# CNTL.net
KiCad netlist of a schematic drawn in Altium Designer
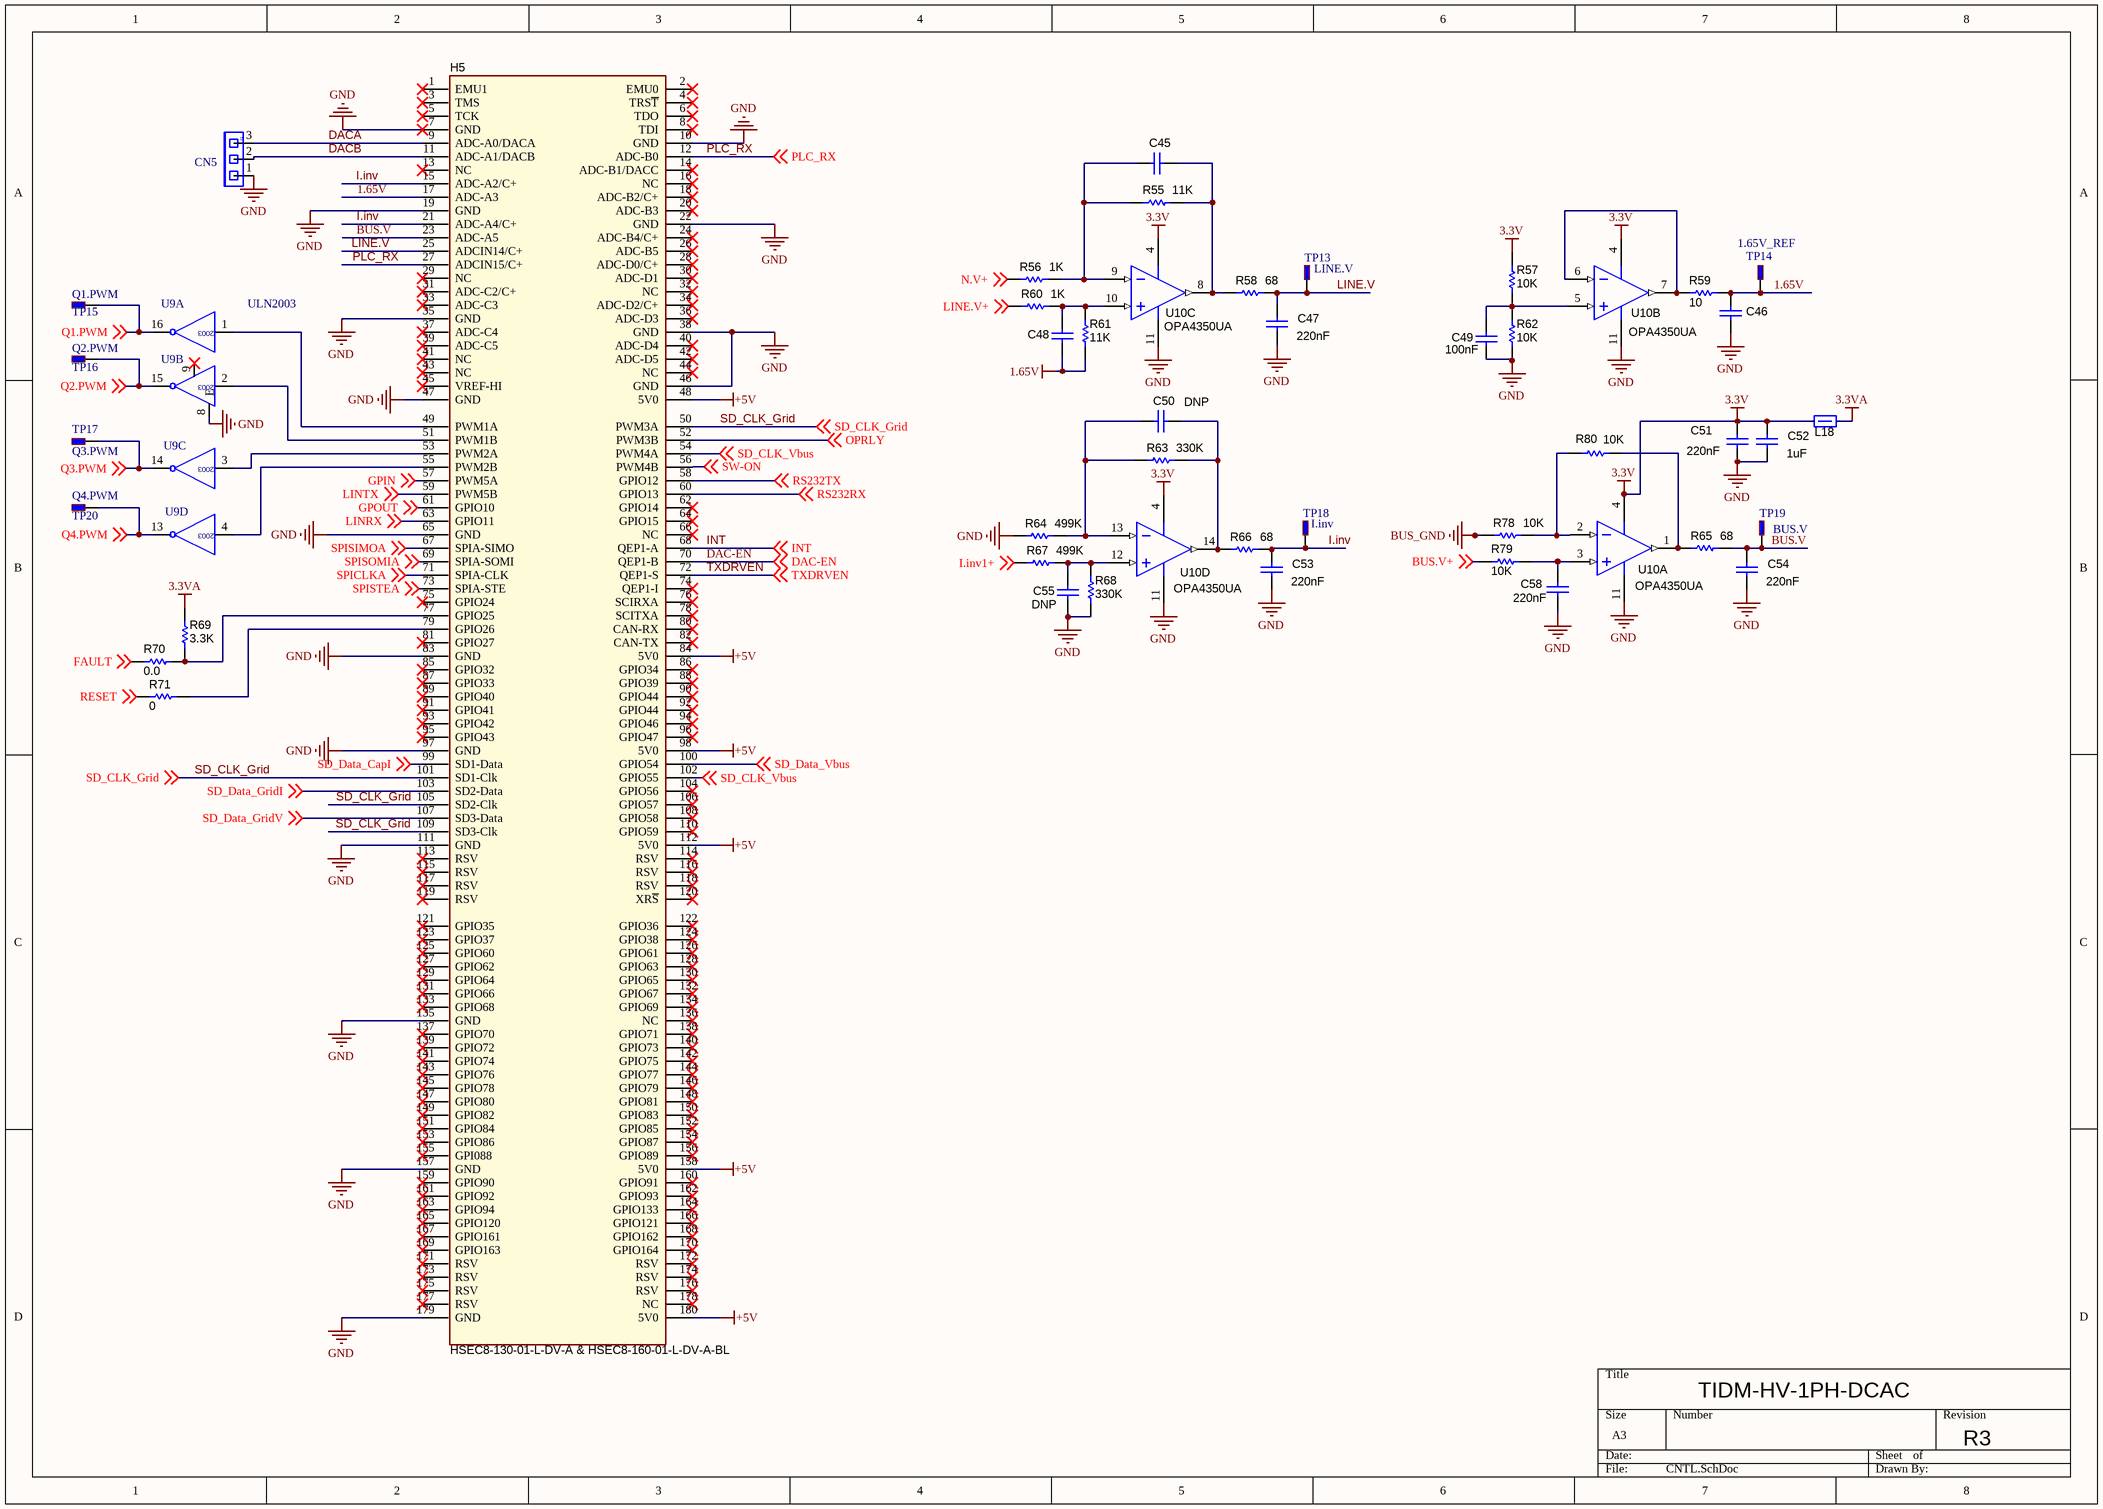
[diagram p0: CNTL.SchDoc]

(export (version "E")
  (design (tool "Eeschema 10.0.6"))
  (components
    (comp (ref "C45")
      (value "Used in BOM report")
      (footprint "0603")
      (description "CAP, CERM, xxxF, xxV, [TempCo], xx%, [PackageReference]")
      (fields (field (name "PUBLISHER") "Texas Instruments"))
      (libsource (lib "MiscParts") (part "Capacitor"))
    )
    (comp (ref "C46")
      (value "Used in BOM report")
      (footprint "0603")
      (description "CAP, CERM, xxxF, xxV, [TempCo], xx%, [PackageReference]")
      (fields (field (name "PUBLISHER") "Texas Instruments"))
      (libsource (lib "MiscParts") (part "Capacitor"))
    )
    (comp (ref "C47")
      (value "220nF")
      (footprint "0603")
      (description "CAP, CERM, xxxF, xxV, [TempCo], xx%, [PackageReference]")
      (fields
        (field (name "MANUFACTURER") "Used in BOM report")
        (field (name "PUBLISHER") "Texas Instruments")
      )
      (libsource (lib "MiscParts") (part "Capacitor"))
    )
    (comp (ref "C48")
      (value "Used in BOM report")
      (footprint "0603")
      (description "CAP, CERM, xxxF, xxV, [TempCo], xx%, [PackageReference]")
      (fields (field (name "PUBLISHER") "Texas Instruments"))
      (libsource (lib "MiscParts") (part "Capacitor"))
    )
    (comp (ref "C49")
      (value "100nF")
      (footprint "0603")
      (description "CAP, CERM, xxxF, xxV, [TempCo], xx%, [PackageReference]")
      (fields
        (field (name "MANUFACTURER") "Used in BOM report")
        (field (name "PUBLISHER") "Texas Instruments")
      )
      (libsource (lib "MiscParts") (part "Capacitor"))
    )
    (comp (ref "C50")
      (value "DNP")
      (footprint "0603")
      (description "CAP, CERM, xxxF, xxV, [TempCo], xx%, [PackageReference]")
      (fields
        (field (name "MANUFACTURER") "Used in BOM report")
        (field (name "PUBLISHER") "Texas Instruments")
      )
      (libsource (lib "MiscParts") (part "Capacitor"))
    )
    (comp (ref "C51")
      (value "220nF")
      (footprint "0603")
      (description "CAP, CERM, xxxF, xxV, [TempCo], xx%, [PackageReference]")
      (fields
        (field (name "MANUFACTURER") "Used in BOM report")
        (field (name "PUBLISHER") "Texas Instruments")
      )
      (libsource (lib "MiscParts") (part "Capacitor"))
    )
    (comp (ref "C52")
      (value "1uF")
      (footprint "0603")
      (description "CAP, CERM, xxxF, xxV, [TempCo], xx%, [PackageReference]")
      (fields
        (field (name "MANUFACTURER") "Used in BOM report")
        (field (name "PUBLISHER") "Texas Instruments")
      )
      (libsource (lib "MiscParts") (part "Capacitor"))
    )
    (comp (ref "C53")
      (value "220nF")
      (footprint "0603")
      (description "CAP, CERM, xxxF, xxV, [TempCo], xx%, [PackageReference]")
      (fields
        (field (name "MANUFACTURER") "Used in BOM report")
        (field (name "PUBLISHER") "Texas Instruments")
      )
      (libsource (lib "MiscParts") (part "Capacitor"))
    )
    (comp (ref "C54")
      (value "220nF")
      (footprint "0603")
      (description "CAP, CERM, xxxF, xxV, [TempCo], xx%, [PackageReference]")
      (fields
        (field (name "MANUFACTURER") "Used in BOM report")
        (field (name "PUBLISHER") "Texas Instruments")
      )
      (libsource (lib "MiscParts") (part "Capacitor"))
    )
    (comp (ref "C55")
      (value "DNP")
      (footprint "0603")
      (description "CAP, CERM, xxxF, xxV, [TempCo], xx%, [PackageReference]")
      (fields
        (field (name "MANUFACTURER") "Used in BOM report")
        (field (name "PUBLISHER") "Texas Instruments")
      )
      (libsource (lib "MiscParts") (part "Capacitor"))
    )
    (comp (ref "C58")
      (value "220nF")
      (footprint "0603")
      (description "CAP, CERM, xxxF, xxV, [TempCo], xx%, [PackageReference]")
      (fields
        (field (name "MANUFACTURER") "Used in BOM report")
        (field (name "PUBLISHER") "Texas Instruments")
      )
      (libsource (lib "MiscParts") (part "Capacitor"))
    )
    (comp (ref "CN5")
      (value "SCI_PORT")
      (footprint "HDR1X3")
      (description "DB01P03")
      (libsource (lib "AD-DIPWIN") (part "DB01P03"))
    )
    (comp (ref "H5")
      (value "HSEC8-130-01-L-DV-A & HSEC8-160-01-L-DV-A-BL")
      (footprint "HEADER_HSEC8_180_DV")
      (fields (field (name "MANUFACTURER") "Samtech") (field (name "SYMBOLCREATOR") "Use a-id"))
      (libsource (lib "controlCARDDockingStationR4_1") (part "HEADER_HSEC_180_F2837x_HVDCACSolar"))
    )
    (comp (ref "L18")
      (value "LQM21FN220N00L")
      (footprint "0805")
      (description "Ferrite Bead, 30 ohm @ 100MHz, 1.5A, 0805")
      (fields (field (name "MANUFACTURER") "Murata") (field (name "PUBLISHER") "Texas Instruments"))
      (libsource (lib "FerriteBead") (part "MMZ2012R300A"))
    )
    (comp (ref "R55")
      (value "11K")
      (footprint "0603")
      (description "RES, 1K ohm, x%, xW, [PackageReference]")
      (fields
        (field (name "MANUFACTURER") "Used in BOM report")
        (field (name "PUBLISHER") "Texas Instruments")
      )
      (libsource (lib "MiscParts") (part "Resistor"))
    )
    (comp (ref "R56")
      (value "1K")
      (footprint "0603")
      (description "RES, 1K ohm, x%, xW, [PackageReference]")
      (fields
        (field (name "MANUFACTURER") "Used in BOM report")
        (field (name "PUBLISHER") "Texas Instruments")
      )
      (libsource (lib "MiscParts") (part "Resistor"))
    )
    (comp (ref "R57")
      (value "10K")
      (footprint "0603")
      (description "RES, 10K ohm, x%, xW, [PackageReference]")
      (fields
        (field (name "MANUFACTURER") "Used in BOM report")
        (field (name "PUBLISHER") "Texas Instruments")
      )
      (libsource (lib "MiscParts") (part "Resistor"))
    )
    (comp (ref "R58")
      (value "68")
      (footprint "0603")
      (description "RES, 1K ohm, x%, xW, [PackageReference]")
      (fields
        (field (name "MANUFACTURER") "Used in BOM report")
        (field (name "PUBLISHER") "Texas Instruments")
      )
      (libsource (lib "MiscParts") (part "Resistor"))
    )
    (comp (ref "R59")
      (value "10")
      (footprint "0603")
      (description "RES, 1K ohm, x%, xW, [PackageReference]")
      (fields
        (field (name "MANUFACTURER") "Used in BOM report")
        (field (name "PUBLISHER") "Texas Instruments")
      )
      (libsource (lib "MiscParts") (part "Resistor"))
    )
    (comp (ref "R60")
      (value "1K")
      (footprint "0603")
      (description "RES, 1K ohm, x%, xW, [PackageReference]")
      (fields
        (field (name "MANUFACTURER") "Used in BOM report")
        (field (name "PUBLISHER") "Texas Instruments")
      )
      (libsource (lib "MiscParts") (part "Resistor"))
    )
    (comp (ref "R61")
      (value "11K")
      (footprint "0603")
      (description "RES, 1K ohm, x%, xW, [PackageReference]")
      (fields
        (field (name "MANUFACTURER") "Used in BOM report")
        (field (name "PUBLISHER") "Texas Instruments")
      )
      (libsource (lib "MiscParts") (part "Resistor"))
    )
    (comp (ref "R62")
      (value "10K")
      (footprint "0603")
      (description "RES, 10K ohm, x%, xW, [PackageReference]")
      (fields
        (field (name "MANUFACTURER") "Used in BOM report")
        (field (name "PUBLISHER") "Texas Instruments")
      )
      (libsource (lib "MiscParts") (part "Resistor"))
    )
    (comp (ref "R63")
      (value "330K")
      (footprint "0603")
      (description "RES, 330K ohm, x%, xW, [PackageReference]")
      (fields
        (field (name "MANUFACTURER") "Used in BOM report")
        (field (name "PUBLISHER") "Texas Instruments")
      )
      (libsource (lib "MiscParts") (part "Resistor"))
    )
    (comp (ref "R64")
      (value "499K")
      (footprint "0603")
      (description "RES, 499K ohm, x%, xW, [PackageReference]")
      (fields
        (field (name "MANUFACTURER") "Used in BOM report")
        (field (name "PUBLISHER") "Texas Instruments")
      )
      (libsource (lib "MiscParts") (part "Resistor"))
    )
    (comp (ref "R65")
      (value "68")
      (footprint "0603")
      (description "RES, 1K ohm, x%, xW, [PackageReference]")
      (fields
        (field (name "MANUFACTURER") "Used in BOM report")
        (field (name "PUBLISHER") "Texas Instruments")
      )
      (libsource (lib "MiscParts") (part "Resistor"))
    )
    (comp (ref "R66")
      (value "68")
      (footprint "0603")
      (description "RES, 1K ohm, x%, xW, [PackageReference]")
      (fields
        (field (name "MANUFACTURER") "Used in BOM report")
        (field (name "PUBLISHER") "Texas Instruments")
      )
      (libsource (lib "MiscParts") (part "Resistor"))
    )
    (comp (ref "R67")
      (value "499K")
      (footprint "0603")
      (description "RES, 499K ohm, x%, xW, [PackageReference]")
      (fields
        (field (name "MANUFACTURER") "Used in BOM report")
        (field (name "PUBLISHER") "Texas Instruments")
      )
      (libsource (lib "MiscParts") (part "Resistor"))
    )
    (comp (ref "R68")
      (value "330K")
      (footprint "0603")
      (description "RES, 330K ohm, x%, xW, [PackageReference]")
      (fields
        (field (name "MANUFACTURER") "Used in BOM report")
        (field (name "PUBLISHER") "Texas Instruments")
      )
      (libsource (lib "MiscParts") (part "Resistor"))
    )
    (comp (ref "R69")
      (value "3.3K")
      (footprint "0805")
      (description "RES, 3.3Kohm, 5%, 0.125W, 0805")
      (fields
        (field (name "PARTNUMBER") "RC0805JR-071R1L")
        (field (name "MANUFACTURER") "Yageo America")
        (field (name "PUBLISHER") "Texas Instruments")
      )
      (libsource (lib "Resistor_0805") (part "RC0805JR-071R1L"))
    )
    (comp (ref "R70")
      (value "0.0")
      (footprint "0805")
      (description "RES, 0 ohm, 5%, 0.125W, 0805")
      (fields
        (field (name "PARTNUMBER") "RC0805JR-071R1L")
        (field (name "MANUFACTURER") "Yageo America")
        (field (name "PUBLISHER") "Texas Instruments")
      )
      (libsource (lib "Resistor_0805") (part "RC0805JR-071R1L"))
    )
    (comp (ref "R71")
      (value "0")
      (footprint "0805")
      (description "RES, 0.0 ohm, 5%, 0.125W, 0805")
      (fields
        (field (name "PARTNUMBER") "RC0805JR-071R1L")
        (field (name "MANUFACTURER") "Yageo America")
        (field (name "PUBLISHER") "Texas Instruments")
      )
      (libsource (lib "Resistor_0805") (part "RC0805JR-071R1L"))
    )
    (comp (ref "R78")
      (value "10K")
      (footprint "0603")
      (description "RES, 1K ohm, x%, xW, [PackageReference]")
      (fields
        (field (name "MANUFACTURER") "Used in BOM report")
        (field (name "PUBLISHER") "Texas Instruments")
      )
      (libsource (lib "MiscParts") (part "Resistor"))
    )
    (comp (ref "R79")
      (value "10K")
      (footprint "0603")
      (description "RES, 1K ohm, x%, xW, [PackageReference]")
      (fields
        (field (name "MANUFACTURER") "Used in BOM report")
        (field (name "PUBLISHER") "Texas Instruments")
      )
      (libsource (lib "MiscParts") (part "Resistor"))
    )
    (comp (ref "R80")
      (value "10K")
      (footprint "0603")
      (description "RES, 1K ohm, x%, xW, [PackageReference]")
      (fields
        (field (name "MANUFACTURER") "Used in BOM report")
        (field (name "PUBLISHER") "Texas Instruments")
      )
      (libsource (lib "MiscParts") (part "Resistor"))
    )
    (comp (ref "TP13")
      (value "LINE.V")
      (footprint "PIN1")
      (description "ZR")
      (libsource (lib "*") (part "PIN1"))
    )
    (comp (ref "TP14")
      (value "1.65V_REF")
      (footprint "PIN1")
      (description "ZR")
      (libsource (lib "*") (part "PIN1"))
    )
    (comp (ref "TP15")
      (value "Q1.PWM")
      (footprint "PIN1")
      (description "ZR")
      (libsource (lib "") (part "PIN1_2"))
    )
    (comp (ref "TP16")
      (value "Q2.PWM")
      (footprint "PIN1")
      (description "ZR")
      (libsource (lib "") (part "PIN1_1"))
    )
    (comp (ref "TP17")
      (value "Q3.PWM")
      (footprint "PIN1")
      (description "ZR")
      (libsource (lib "") (part "PIN1_2"))
    )
    (comp (ref "TP18")
      (value "I.inv")
      (footprint "PIN1")
      (description "ZR")
      (libsource (lib "*") (part "PIN1"))
    )
    (comp (ref "TP19")
      (value "BUS.V")
      (footprint "PIN1")
      (description "ZR")
      (libsource (lib "*") (part "PIN1"))
    )
    (comp (ref "TP20")
      (value "Q4.PWM")
      (footprint "PIN1")
      (description "ZR")
      (libsource (lib "") (part "PIN1_1"))
    )
    (comp (ref "U9")
      (value "ULN2003")
      (footprint "2003SM")
      (description "2003SM")
      (libsource (lib "") (part "2003SM_1"))
    )
    (comp (ref "U10")
      (value "OPA4350UA")
      (footprint "D0014A_N")
      (fields
        (field (name "MANUFACTURER") "Texas Instruments")
        (field (name "ALTERNATE PARTNUMBER") "Equivalent")
      )
      (libsource (lib "TI Amplifiers and Linear Operational Amplifier Precision Amplifier Part One") (part "OPA4350UA"))
    )
  )
  (nets
    (net (code "1") (name "+5V") (class "Default")
      (node (ref "H5") (pin "112") (pinfunction "5V0_112") (pintype "passive"))
      (node (ref "H5") (pin "158") (pinfunction "5V0_158") (pintype "passive"))
      (node (ref "H5") (pin "180") (pinfunction "5V0_180") (pintype "passive"))
      (node (ref "H5") (pin "48") (pinfunction "5V0_48") (pintype "passive"))
      (node (ref "H5") (pin "84") (pinfunction "5V0_84") (pintype "passive"))
      (node (ref "H5") (pin "98") (pinfunction "5V0_98") (pintype "passive"))
    )
    (net (code "3") (name "/BUS.V") (class "Default")
      (node (ref "C54") (pin "1") (pinfunction "1_1") (pintype "passive"))
      (node (ref "H5") (pin "23") (pinfunction "ADC-A5_23") (pintype "passive"))
      (node (ref "R65") (pin "2") (pinfunction "2_2") (pintype "passive"))
      (node (ref "TP19") (pin "1") (pinfunction "1_1") (pintype "passive"))
    )
    (net (code "4") (name "/DACA") (class "Default")
      (node (ref "CN5") (pin "3") (pintype "passive"))
      (node (ref "H5") (pin "9") (pinfunction "ADC-A0/DACA_9") (pintype "passive"))
    )
    (net (code "5") (name "/DACB") (class "Default")
      (node (ref "CN5") (pin "2") (pintype "passive"))
      (node (ref "H5") (pin "11") (pinfunction "ADC-A1/DACB_11") (pintype "passive"))
    )
    (net (code "6") (name "/I.inv") (class "Default")
      (node (ref "C53") (pin "1") (pinfunction "1_1") (pintype "passive"))
      (node (ref "H5") (pin "15") (pinfunction "ADC-A2/C+_15") (pintype "passive"))
      (node (ref "H5") (pin "21") (pinfunction "ADC-A4/C+_21") (pintype "passive"))
      (node (ref "R66") (pin "2") (pinfunction "2_2") (pintype "passive"))
      (node (ref "TP18") (pin "1") (pinfunction "1_1") (pintype "passive"))
    )
    (net (code "7") (name "/LINE.V") (class "Default")
      (node (ref "C47") (pin "1") (pinfunction "1_1") (pintype "passive"))
      (node (ref "H5") (pin "25") (pinfunction "ADCIN14/C+_25") (pintype "passive"))
      (node (ref "R58") (pin "2") (pinfunction "2_2") (pintype "passive"))
      (node (ref "TP13") (pin "1") (pinfunction "1_1") (pintype "passive"))
    )
    (net (code "8") (name "1.65V") (class "Default")
      (node (ref "C46") (pin "1") (pinfunction "1_1") (pintype "passive"))
      (node (ref "C48") (pin "2") (pinfunction "2_2") (pintype "passive"))
      (node (ref "H5") (pin "17") (pinfunction "ADC-A3_17") (pintype "passive"))
      (node (ref "R59") (pin "1") (pinfunction "1_1") (pintype "passive"))
      (node (ref "R61") (pin "1") (pinfunction "1_1") (pintype "passive"))
      (node (ref "TP14") (pin "1") (pinfunction "1_1") (pintype "passive"))
    )
    (net (code "9") (name "3.3V") (class "Default")
      (node (ref "C51") (pin "1") (pinfunction "1_1") (pintype "passive"))
      (node (ref "C52") (pin "1") (pinfunction "1_1") (pintype "passive"))
      (node (ref "L18") (pin "2") (pinfunction "2_2") (pintype "passive"))
      (node (ref "R57") (pin "2") (pinfunction "2_2") (pintype "passive"))
      (node (ref "U10") (pin "4") (pinfunction "V+_4") (pintype "power_in"))
    )
    (net (code "10") (name "3.3VA") (class "Default")
      (node (ref "L18") (pin "1") (pinfunction "1_1") (pintype "passive"))
      (node (ref "R69") (pin "2") (pinfunction "2_2") (pintype "passive"))
    )
    (net (code "11") (name "BUS.V+") (class "Default")
      (node (ref "R79") (pin "2") (pinfunction "2_2") (pintype "passive"))
    )
    (net (code "12") (name "BUS_GND") (class "Default")
      (node (ref "R78") (pin "1") (pinfunction "1_1") (pintype "passive"))
    )
    (net (code "13") (name "COM") (class "Default")
      (node (ref "U9") (pin "9") (pinfunction "COM_9") (pintype "power_in"))
    )
    (net (code "14") (name "DAC-EN") (class "Default")
      (node (ref "H5") (pin "70") (pinfunction "QEP1-B_70") (pintype "passive"))
    )
    (net (code "15") (name "E") (class "Default")
      (node (ref "U9") (pin "8") (pinfunction "E_8") (pintype "power_in"))
    )
    (net (code "16") (name "FAULT") (class "Default")
      (node (ref "R70") (pin "1") (pinfunction "1_1") (pintype "passive"))
    )
    (net (code "17") (name "GND") (class "Default")
      (node (ref "C46") (pin "2") (pinfunction "2_2") (pintype "passive"))
      (node (ref "C47") (pin "2") (pinfunction "2_2") (pintype "passive"))
      (node (ref "C49") (pin "2") (pinfunction "2_2") (pintype "passive"))
      (node (ref "C51") (pin "2") (pinfunction "2_2") (pintype "passive"))
      (node (ref "C52") (pin "2") (pinfunction "2_2") (pintype "passive"))
      (node (ref "C53") (pin "2") (pinfunction "2_2") (pintype "passive"))
      (node (ref "C54") (pin "2") (pinfunction "2_2") (pintype "passive"))
      (node (ref "C55") (pin "2") (pinfunction "2_2") (pintype "passive"))
      (node (ref "C58") (pin "2") (pinfunction "2_2") (pintype "passive"))
      (node (ref "CN5") (pin "1") (pintype "passive"))
      (node (ref "H5") (pin "10") (pinfunction "GND_10") (pintype "passive"))
      (node (ref "H5") (pin "111") (pinfunction "GND_111") (pintype "passive"))
      (node (ref "H5") (pin "135") (pinfunction "GND_135") (pintype "passive"))
      (node (ref "H5") (pin "157") (pinfunction "GND_157") (pintype "passive"))
      (node (ref "H5") (pin "179") (pinfunction "GND_179") (pintype "passive"))
      (node (ref "H5") (pin "19") (pinfunction "GND_19") (pintype "passive"))
      (node (ref "H5") (pin "22") (pinfunction "GND_22") (pintype "passive"))
      (node (ref "H5") (pin "35") (pinfunction "GND_35") (pintype "passive"))
      (node (ref "H5") (pin "38") (pinfunction "GND_38") (pintype "passive"))
      (node (ref "H5") (pin "46") (pinfunction "GND_46") (pintype "passive"))
      (node (ref "H5") (pin "47") (pinfunction "GND_47") (pintype "passive"))
      (node (ref "H5") (pin "65") (pinfunction "GND_65") (pintype "passive"))
      (node (ref "H5") (pin "7") (pinfunction "GND_7") (pintype "passive"))
      (node (ref "H5") (pin "83") (pinfunction "GND_83") (pintype "passive"))
      (node (ref "H5") (pin "97") (pinfunction "GND_97") (pintype "passive"))
      (node (ref "R62") (pin "1") (pinfunction "1_1") (pintype "passive"))
      (node (ref "R64") (pin "1") (pinfunction "1_1") (pintype "passive"))
      (node (ref "R68") (pin "1") (pinfunction "1_1") (pintype "passive"))
      (node (ref "U10") (pin "11") (pinfunction "V-_11") (pintype "power_in"))
      (node (ref "U9") (pin "8") (pinfunction "E_8") (pintype "power_in"))
    )
    (net (code "18") (name "GPIN") (class "Default")
      (node (ref "H5") (pin "57") (pinfunction "PWM5A_57") (pintype "passive"))
    )
    (net (code "19") (name "GPOUT") (class "Default")
      (node (ref "H5") (pin "61") (pinfunction "GPIO10_61") (pintype "passive"))
    )
    (net (code "20") (name "I.inv1+") (class "Default")
      (node (ref "R67") (pin "1") (pinfunction "1_1") (pintype "passive"))
    )
    (net (code "21") (name "INT") (class "Default")
      (node (ref "H5") (pin "68") (pinfunction "QEP1-A_68") (pintype "passive"))
    )
    (net (code "22") (name "LINE.V+") (class "Default")
      (node (ref "R60") (pin "1") (pinfunction "1_1") (pintype "passive"))
    )
    (net (code "23") (name "LINRX") (class "Default")
      (node (ref "H5") (pin "63") (pinfunction "GPIO11_63") (pintype "passive"))
    )
    (net (code "24") (name "LINTX") (class "Default")
      (node (ref "H5") (pin "59") (pinfunction "PWM5B_59") (pintype "passive"))
    )
    (net (code "25") (name "N.V+") (class "Default")
      (node (ref "R56") (pin "1") (pinfunction "1_1") (pintype "passive"))
    )
    (net (code "26") (name "Net-(H5-GPIO25)") (class "Default")
      (node (ref "H5") (pin "77") (pinfunction "GPIO25_77") (pintype "passive"))
      (node (ref "R69") (pin "1") (pinfunction "1_1") (pintype "passive"))
      (node (ref "R70") (pin "2") (pinfunction "2_2") (pintype "passive"))
    )
    (net (code "27") (name "Net-(H5-GPIO26)") (class "Default")
      (node (ref "H5") (pin "79") (pinfunction "GPIO26_79") (pintype "passive"))
      (node (ref "R71") (pin "2") (pinfunction "2_2") (pintype "passive"))
    )
    (net (code "28") (name "Net-(H5-PWM1A)") (class "Default")
      (node (ref "H5") (pin "49") (pinfunction "PWM1A_49") (pintype "passive"))
      (node (ref "U9") (pin "1") (pinfunction "1_1") (pintype "passive"))
    )
    (net (code "29") (name "Net-(H5-PWM1B)") (class "Default")
      (node (ref "H5") (pin "51") (pinfunction "PWM1B_51") (pintype "passive"))
      (node (ref "U9") (pin "2") (pinfunction "2_2") (pintype "passive"))
    )
    (net (code "30") (name "Net-(H5-PWM2A)") (class "Default")
      (node (ref "H5") (pin "53") (pinfunction "PWM2A_53") (pintype "passive"))
      (node (ref "U9") (pin "3") (pinfunction "3_3") (pintype "passive"))
    )
    (net (code "31") (name "Net-(H5-PWM2B)") (class "Default")
      (node (ref "H5") (pin "55") (pinfunction "PWM2B_55") (pintype "passive"))
      (node (ref "U9") (pin "4") (pinfunction "4_4") (pintype "passive"))
    )
    (net (code "32") (name "Net-(U10A-IN_A+)") (class "Default")
      (node (ref "C58") (pin "1") (pinfunction "1_1") (pintype "passive"))
      (node (ref "R79") (pin "1") (pinfunction "1_1") (pintype "passive"))
      (node (ref "U10") (pin "3") (pinfunction "IN_A+_3") (pintype "input"))
    )
    (net (code "33") (name "Net-(U10A-IN_A-)") (class "Default")
      (node (ref "R78") (pin "2") (pinfunction "2_2") (pintype "passive"))
      (node (ref "R80") (pin "1") (pinfunction "1_1") (pintype "passive"))
      (node (ref "U10") (pin "2") (pinfunction "IN_A-_2") (pintype "input"))
    )
    (net (code "34") (name "Net-(U10A-OUT_A)") (class "Default")
      (node (ref "R65") (pin "1") (pinfunction "1_1") (pintype "passive"))
      (node (ref "R80") (pin "2") (pinfunction "2_2") (pintype "passive"))
      (node (ref "U10") (pin "1") (pinfunction "OUT_A_1") (pintype "output"))
    )
    (net (code "35") (name "Net-(U10B-IN_B+)") (class "Default")
      (node (ref "C49") (pin "1") (pinfunction "1_1") (pintype "passive"))
      (node (ref "R57") (pin "1") (pinfunction "1_1") (pintype "passive"))
      (node (ref "R62") (pin "2") (pinfunction "2_2") (pintype "passive"))
      (node (ref "U10") (pin "5") (pinfunction "IN_B+_5") (pintype "input"))
    )
    (net (code "36") (name "Net-(U10B-IN_B-)") (class "Default")
      (node (ref "R59") (pin "2") (pinfunction "2_2") (pintype "passive"))
      (node (ref "U10") (pin "6") (pinfunction "IN_B-_6") (pintype "input"))
      (node (ref "U10") (pin "7") (pinfunction "OUT_B_7") (pintype "output"))
    )
    (net (code "37") (name "Net-(U10C-IN_C+)") (class "Default")
      (node (ref "C48") (pin "1") (pinfunction "1_1") (pintype "passive"))
      (node (ref "R60") (pin "2") (pinfunction "2_2") (pintype "passive"))
      (node (ref "R61") (pin "2") (pinfunction "2_2") (pintype "passive"))
      (node (ref "U10") (pin "10") (pinfunction "IN_C+_10") (pintype "input"))
    )
    (net (code "38") (name "Net-(U10C-IN_C-)") (class "Default")
      (node (ref "C45") (pin "1") (pinfunction "1_1") (pintype "passive"))
      (node (ref "R55") (pin "1") (pinfunction "1_1") (pintype "passive"))
      (node (ref "R56") (pin "2") (pinfunction "2_2") (pintype "passive"))
      (node (ref "U10") (pin "9") (pinfunction "IN_C-_9") (pintype "input"))
    )
    (net (code "39") (name "Net-(U10C-OUT_C)") (class "Default")
      (node (ref "C45") (pin "2") (pinfunction "2_2") (pintype "passive"))
      (node (ref "R55") (pin "2") (pinfunction "2_2") (pintype "passive"))
      (node (ref "R58") (pin "1") (pinfunction "1_1") (pintype "passive"))
      (node (ref "U10") (pin "8") (pinfunction "OUT_C_8") (pintype "output"))
    )
    (net (code "40") (name "Net-(U10D-IN_D+)") (class "Default")
      (node (ref "C55") (pin "1") (pinfunction "1_1") (pintype "passive"))
      (node (ref "R67") (pin "2") (pinfunction "2_2") (pintype "passive"))
      (node (ref "R68") (pin "2") (pinfunction "2_2") (pintype "passive"))
      (node (ref "U10") (pin "12") (pinfunction "IN_D+_12") (pintype "input"))
    )
    (net (code "41") (name "Net-(U10D-IN_D-)") (class "Default")
      (node (ref "C50") (pin "1") (pinfunction "1_1") (pintype "passive"))
      (node (ref "R63") (pin "1") (pinfunction "1_1") (pintype "passive"))
      (node (ref "R64") (pin "2") (pinfunction "2_2") (pintype "passive"))
      (node (ref "U10") (pin "13") (pinfunction "IN_D-_13") (pintype "input"))
    )
    (net (code "42") (name "Net-(U10D-OUT_D)") (class "Default")
      (node (ref "C50") (pin "2") (pinfunction "2_2") (pintype "passive"))
      (node (ref "R63") (pin "2") (pinfunction "2_2") (pintype "passive"))
      (node (ref "R66") (pin "1") (pinfunction "1_1") (pintype "passive"))
      (node (ref "U10") (pin "14") (pinfunction "OUT_D_14") (pintype "output"))
    )
    (net (code "43") (name "OPRLY") (class "Default")
      (node (ref "H5") (pin "52") (pinfunction "PWM3B_52") (pintype "passive"))
    )
    (net (code "44") (name "PLC_RX") (class "Default")
      (node (ref "H5") (pin "12") (pinfunction "ADC-B0_12") (pintype "passive"))
      (node (ref "H5") (pin "27") (pinfunction "ADCIN15/C+_27") (pintype "passive"))
    )
    (net (code "45") (name "Q1.PWM") (class "Default")
      (node (ref "TP15") (pin "1") (pinfunction "1_1") (pintype "passive"))
      (node (ref "U9") (pin "16") (pinfunction "1_16") (pintype "passive"))
    )
    (net (code "46") (name "Q2.PWM") (class "Default")
      (node (ref "TP16") (pin "1") (pinfunction "1_1") (pintype "passive"))
      (node (ref "U9") (pin "15") (pinfunction "2_15") (pintype "passive"))
    )
    (net (code "47") (name "Q3.PWM") (class "Default")
      (node (ref "TP17") (pin "1") (pinfunction "1_1") (pintype "passive"))
      (node (ref "U9") (pin "14") (pinfunction "3_14") (pintype "passive"))
    )
    (net (code "48") (name "Q4.PWM") (class "Default")
      (node (ref "TP20") (pin "1") (pinfunction "1_1") (pintype "passive"))
      (node (ref "U9") (pin "13") (pinfunction "4_13") (pintype "passive"))
    )
    (net (code "49") (name "RESET") (class "Default")
      (node (ref "R71") (pin "1") (pinfunction "1_1") (pintype "passive"))
    )
    (net (code "50") (name "RS232RX") (class "Default")
      (node (ref "H5") (pin "60") (pinfunction "GPIO13_60") (pintype "passive"))
    )
    (net (code "51") (name "RS232TX") (class "Default")
      (node (ref "H5") (pin "58") (pinfunction "GPIO12_58") (pintype "passive"))
    )
    (net (code "52") (name "SD_CLK_Grid") (class "Default")
      (node (ref "H5") (pin "101") (pinfunction "SD1-Clk_101") (pintype "passive"))
      (node (ref "H5") (pin "105") (pinfunction "SD2-Clk_105") (pintype "passive"))
      (node (ref "H5") (pin "109") (pinfunction "SD3-Clk_109") (pintype "passive"))
      (node (ref "H5") (pin "50") (pinfunction "PWM3A_50") (pintype "passive"))
    )
    (net (code "53") (name "SD_CLK_Vbus") (class "Default")
      (node (ref "H5") (pin "102") (pinfunction "GPIO55_102") (pintype "passive"))
      (node (ref "H5") (pin "54") (pinfunction "PWM4A_54") (pintype "passive"))
    )
    (net (code "54") (name "SD_Data_CapI") (class "Default")
      (node (ref "H5") (pin "99") (pinfunction "SD1-Data_99") (pintype "passive"))
    )
    (net (code "55") (name "SD_Data_GridI") (class "Default")
      (node (ref "H5") (pin "103") (pinfunction "SD2-Data_103") (pintype "passive"))
    )
    (net (code "56") (name "SD_Data_GridV") (class "Default")
      (node (ref "H5") (pin "107") (pinfunction "SD3-Data_107") (pintype "passive"))
    )
    (net (code "57") (name "SD_Data_Vbus") (class "Default")
      (node (ref "H5") (pin "100") (pinfunction "GPIO54_100") (pintype "passive"))
    )
    (net (code "58") (name "SPICLKA") (class "Default")
      (node (ref "H5") (pin "71") (pinfunction "SPIA-CLK_71") (pintype "passive"))
    )
    (net (code "59") (name "SPISIMOA") (class "Default")
      (node (ref "H5") (pin "67") (pinfunction "SPIA-SIMO_67") (pintype "passive"))
    )
    (net (code "60") (name "SPISOMIA") (class "Default")
      (node (ref "H5") (pin "69") (pinfunction "SPIA-SOMI_69") (pintype "passive"))
    )
    (net (code "61") (name "SPISTEA") (class "Default")
      (node (ref "H5") (pin "73") (pinfunction "SPIA-STE_73") (pintype "passive"))
    )
    (net (code "62") (name "SW-ON") (class "Default")
      (node (ref "H5") (pin "56") (pinfunction "PWM4B_56") (pintype "passive"))
    )
    (net (code "63") (name "TXDRVEN") (class "Default")
      (node (ref "H5") (pin "72") (pinfunction "QEP1-S_72") (pintype "passive"))
    )
    (net (code "64") (name "unconnected-(H5-ADC-B1{slash}DACC-Pad14)") (class "Default")
      (node (ref "H5") (pin "14") (pinfunction "ADC-B1/DACC_14") (pintype "passive+no_connect"))
    )
    (net (code "65") (name "unconnected-(H5-ADC-B2{slash}C+-Pad18)") (class "Default")
      (node (ref "H5") (pin "18") (pinfunction "ADC-B2/C+_18") (pintype "passive+no_connect"))
    )
    (net (code "66") (name "unconnected-(H5-ADC-B3-Pad20)") (class "Default")
      (node (ref "H5") (pin "20") (pinfunction "ADC-B3_20") (pintype "passive+no_connect"))
    )
    (net (code "67") (name "unconnected-(H5-ADC-B4{slash}C+-Pad24)") (class "Default")
      (node (ref "H5") (pin "24") (pinfunction "ADC-B4/C+_24") (pintype "passive+no_connect"))
    )
    (net (code "68") (name "unconnected-(H5-ADC-B5-Pad26)") (class "Default")
      (node (ref "H5") (pin "26") (pinfunction "ADC-B5_26") (pintype "passive+no_connect"))
    )
    (net (code "69") (name "unconnected-(H5-ADC-C2{slash}C+-Pad31)") (class "Default")
      (node (ref "H5") (pin "31") (pinfunction "ADC-C2/C+_31") (pintype "passive+no_connect"))
    )
    (net (code "70") (name "unconnected-(H5-ADC-C3-Pad33)") (class "Default")
      (node (ref "H5") (pin "33") (pinfunction "ADC-C3_33") (pintype "passive+no_connect"))
    )
    (net (code "71") (name "unconnected-(H5-ADC-C4-Pad37)") (class "Default")
      (node (ref "H5") (pin "37") (pinfunction "ADC-C4_37") (pintype "passive+no_connect"))
    )
    (net (code "72") (name "unconnected-(H5-ADC-C5-Pad39)") (class "Default")
      (node (ref "H5") (pin "39") (pinfunction "ADC-C5_39") (pintype "passive+no_connect"))
    )
    (net (code "73") (name "unconnected-(H5-ADC-D0{slash}C+-Pad28)") (class "Default")
      (node (ref "H5") (pin "28") (pinfunction "ADC-D0/C+_28") (pintype "passive+no_connect"))
    )
    (net (code "74") (name "unconnected-(H5-ADC-D1-Pad30)") (class "Default")
      (node (ref "H5") (pin "30") (pinfunction "ADC-D1_30") (pintype "passive+no_connect"))
    )
    (net (code "75") (name "unconnected-(H5-ADC-D2{slash}C+-Pad34)") (class "Default")
      (node (ref "H5") (pin "34") (pinfunction "ADC-D2/C+_34") (pintype "passive+no_connect"))
    )
    (net (code "76") (name "unconnected-(H5-ADC-D3-Pad36)") (class "Default")
      (node (ref "H5") (pin "36") (pinfunction "ADC-D3_36") (pintype "passive+no_connect"))
    )
    (net (code "77") (name "unconnected-(H5-ADC-D4-Pad40)") (class "Default")
      (node (ref "H5") (pin "40") (pinfunction "ADC-D4_40") (pintype "passive+no_connect"))
    )
    (net (code "78") (name "unconnected-(H5-ADC-D5-Pad42)") (class "Default")
      (node (ref "H5") (pin "42") (pinfunction "ADC-D5_42") (pintype "passive+no_connect"))
    )
    (net (code "79") (name "unconnected-(H5-CAN-RX-Pad80)") (class "Default")
      (node (ref "H5") (pin "80") (pinfunction "CAN-RX_80") (pintype "passive+no_connect"))
    )
    (net (code "80") (name "unconnected-(H5-CAN-TX-Pad82)") (class "Default")
      (node (ref "H5") (pin "82") (pinfunction "CAN-TX_82") (pintype "passive+no_connect"))
    )
    (net (code "81") (name "unconnected-(H5-EMU0-Pad2)") (class "Default")
      (node (ref "H5") (pin "2") (pinfunction "EMU0_2") (pintype "passive+no_connect"))
    )
    (net (code "82") (name "unconnected-(H5-EMU1-Pad1)") (class "Default")
      (node (ref "H5") (pin "1") (pinfunction "EMU1_1") (pintype "passive+no_connect"))
    )
    (net (code "83") (name "unconnected-(H5-GPI088-Pad155)") (class "Default")
      (node (ref "H5") (pin "155") (pinfunction "GPI088_155") (pintype "passive+no_connect"))
    )
    (net (code "84") (name "unconnected-(H5-GPIO14-Pad62)") (class "Default")
      (node (ref "H5") (pin "62") (pinfunction "GPIO14_62") (pintype "passive+no_connect"))
    )
    (net (code "85") (name "unconnected-(H5-GPIO15-Pad64)") (class "Default")
      (node (ref "H5") (pin "64") (pinfunction "GPIO15_64") (pintype "passive+no_connect"))
    )
    (net (code "86") (name "unconnected-(H5-GPIO24-Pad75)") (class "Default")
      (node (ref "H5") (pin "75") (pinfunction "GPIO24_75") (pintype "passive+no_connect"))
    )
    (net (code "87") (name "unconnected-(H5-GPIO27-Pad81)") (class "Default")
      (node (ref "H5") (pin "81") (pinfunction "GPIO27_81") (pintype "passive+no_connect"))
    )
    (net (code "88") (name "unconnected-(H5-GPIO32-Pad85)") (class "Default")
      (node (ref "H5") (pin "85") (pinfunction "GPIO32_85") (pintype "passive+no_connect"))
    )
    (net (code "89") (name "unconnected-(H5-GPIO33-Pad87)") (class "Default")
      (node (ref "H5") (pin "87") (pinfunction "GPIO33_87") (pintype "passive+no_connect"))
    )
    (net (code "90") (name "unconnected-(H5-GPIO34-Pad86)") (class "Default")
      (node (ref "H5") (pin "86") (pinfunction "GPIO34_86") (pintype "passive+no_connect"))
    )
    (net (code "91") (name "unconnected-(H5-GPIO35-Pad121)") (class "Default")
      (node (ref "H5") (pin "121") (pinfunction "GPIO35_121") (pintype "passive+no_connect"))
    )
    (net (code "92") (name "unconnected-(H5-GPIO36-Pad122)") (class "Default")
      (node (ref "H5") (pin "122") (pinfunction "GPIO36_122") (pintype "passive+no_connect"))
    )
    (net (code "93") (name "unconnected-(H5-GPIO37-Pad123)") (class "Default")
      (node (ref "H5") (pin "123") (pinfunction "GPIO37_123") (pintype "passive+no_connect"))
    )
    (net (code "94") (name "unconnected-(H5-GPIO38-Pad124)") (class "Default")
      (node (ref "H5") (pin "124") (pinfunction "GPIO38_124") (pintype "passive+no_connect"))
    )
    (net (code "95") (name "unconnected-(H5-GPIO39-Pad88)") (class "Default")
      (node (ref "H5") (pin "88") (pinfunction "GPIO39_88") (pintype "passive+no_connect"))
    )
    (net (code "96") (name "unconnected-(H5-GPIO40-Pad89)") (class "Default")
      (node (ref "H5") (pin "89") (pinfunction "GPIO40_89") (pintype "passive+no_connect"))
    )
    (net (code "97") (name "unconnected-(H5-GPIO41-Pad91)") (class "Default")
      (node (ref "H5") (pin "91") (pinfunction "GPIO41_91") (pintype "passive+no_connect"))
    )
    (net (code "98") (name "unconnected-(H5-GPIO42-Pad93)") (class "Default")
      (node (ref "H5") (pin "93") (pinfunction "GPIO42_93") (pintype "passive+no_connect"))
    )
    (net (code "99") (name "unconnected-(H5-GPIO43-Pad95)") (class "Default")
      (node (ref "H5") (pin "95") (pinfunction "GPIO43_95") (pintype "passive+no_connect"))
    )
    (net (code "100") (name "unconnected-(H5-GPIO44-Pad90)") (class "Default")
      (node (ref "H5") (pin "90") (pinfunction "GPIO44_90") (pintype "passive+no_connect"))
    )
    (net (code "101") (name "unconnected-(H5-GPIO44-Pad92)") (class "Default")
      (node (ref "H5") (pin "92") (pinfunction "GPIO44_92") (pintype "passive+no_connect"))
    )
    (net (code "102") (name "unconnected-(H5-GPIO46-Pad94)") (class "Default")
      (node (ref "H5") (pin "94") (pinfunction "GPIO46_94") (pintype "passive+no_connect"))
    )
    (net (code "103") (name "unconnected-(H5-GPIO47-Pad96)") (class "Default")
      (node (ref "H5") (pin "96") (pinfunction "GPIO47_96") (pintype "passive+no_connect"))
    )
    (net (code "104") (name "unconnected-(H5-GPIO56-Pad104)") (class "Default")
      (node (ref "H5") (pin "104") (pinfunction "GPIO56_104") (pintype "passive+no_connect"))
    )
    (net (code "105") (name "unconnected-(H5-GPIO57-Pad106)") (class "Default")
      (node (ref "H5") (pin "106") (pinfunction "GPIO57_106") (pintype "passive+no_connect"))
    )
    (net (code "106") (name "unconnected-(H5-GPIO58-Pad108)") (class "Default")
      (node (ref "H5") (pin "108") (pinfunction "GPIO58_108") (pintype "passive+no_connect"))
    )
    (net (code "107") (name "unconnected-(H5-GPIO59-Pad110)") (class "Default")
      (node (ref "H5") (pin "110") (pinfunction "GPIO59_110") (pintype "passive+no_connect"))
    )
    (net (code "108") (name "unconnected-(H5-GPIO60-Pad125)") (class "Default")
      (node (ref "H5") (pin "125") (pinfunction "GPIO60_125") (pintype "passive+no_connect"))
    )
    (net (code "109") (name "unconnected-(H5-GPIO61-Pad126)") (class "Default")
      (node (ref "H5") (pin "126") (pinfunction "GPIO61_126") (pintype "passive+no_connect"))
    )
    (net (code "110") (name "unconnected-(H5-GPIO62-Pad127)") (class "Default")
      (node (ref "H5") (pin "127") (pinfunction "GPIO62_127") (pintype "passive+no_connect"))
    )
    (net (code "111") (name "unconnected-(H5-GPIO63-Pad128)") (class "Default")
      (node (ref "H5") (pin "128") (pinfunction "GPIO63_128") (pintype "passive+no_connect"))
    )
    (net (code "112") (name "unconnected-(H5-GPIO64-Pad129)") (class "Default")
      (node (ref "H5") (pin "129") (pinfunction "GPIO64_129") (pintype "passive+no_connect"))
    )
    (net (code "113") (name "unconnected-(H5-GPIO65-Pad130)") (class "Default")
      (node (ref "H5") (pin "130") (pinfunction "GPIO65_130") (pintype "passive+no_connect"))
    )
    (net (code "114") (name "unconnected-(H5-GPIO66-Pad131)") (class "Default")
      (node (ref "H5") (pin "131") (pinfunction "GPIO66_131") (pintype "passive+no_connect"))
    )
    (net (code "115") (name "unconnected-(H5-GPIO67-Pad132)") (class "Default")
      (node (ref "H5") (pin "132") (pinfunction "GPIO67_132") (pintype "passive+no_connect"))
    )
    (net (code "116") (name "unconnected-(H5-GPIO68-Pad133)") (class "Default")
      (node (ref "H5") (pin "133") (pinfunction "GPIO68_133") (pintype "passive+no_connect"))
    )
    (net (code "117") (name "unconnected-(H5-GPIO69-Pad134)") (class "Default")
      (node (ref "H5") (pin "134") (pinfunction "GPIO69_134") (pintype "passive+no_connect"))
    )
    (net (code "118") (name "unconnected-(H5-GPIO70-Pad137)") (class "Default")
      (node (ref "H5") (pin "137") (pinfunction "GPIO70_137") (pintype "passive+no_connect"))
    )
    (net (code "119") (name "unconnected-(H5-GPIO71-Pad138)") (class "Default")
      (node (ref "H5") (pin "138") (pinfunction "GPIO71_138") (pintype "passive+no_connect"))
    )
    (net (code "120") (name "unconnected-(H5-GPIO72-Pad139)") (class "Default")
      (node (ref "H5") (pin "139") (pinfunction "GPIO72_139") (pintype "passive+no_connect"))
    )
    (net (code "121") (name "unconnected-(H5-GPIO73-Pad140)") (class "Default")
      (node (ref "H5") (pin "140") (pinfunction "GPIO73_140") (pintype "passive+no_connect"))
    )
    (net (code "122") (name "unconnected-(H5-GPIO74-Pad141)") (class "Default")
      (node (ref "H5") (pin "141") (pinfunction "GPIO74_141") (pintype "passive+no_connect"))
    )
    (net (code "123") (name "unconnected-(H5-GPIO75-Pad142)") (class "Default")
      (node (ref "H5") (pin "142") (pinfunction "GPIO75_142") (pintype "passive+no_connect"))
    )
    (net (code "124") (name "unconnected-(H5-GPIO76-Pad143)") (class "Default")
      (node (ref "H5") (pin "143") (pinfunction "GPIO76_143") (pintype "passive+no_connect"))
    )
    (net (code "125") (name "unconnected-(H5-GPIO77-Pad144)") (class "Default")
      (node (ref "H5") (pin "144") (pinfunction "GPIO77_144") (pintype "passive+no_connect"))
    )
    (net (code "126") (name "unconnected-(H5-GPIO78-Pad145)") (class "Default")
      (node (ref "H5") (pin "145") (pinfunction "GPIO78_145") (pintype "passive+no_connect"))
    )
    (net (code "127") (name "unconnected-(H5-GPIO79-Pad146)") (class "Default")
      (node (ref "H5") (pin "146") (pinfunction "GPIO79_146") (pintype "passive+no_connect"))
    )
    (net (code "128") (name "unconnected-(H5-GPIO80-Pad147)") (class "Default")
      (node (ref "H5") (pin "147") (pinfunction "GPIO80_147") (pintype "passive+no_connect"))
    )
    (net (code "129") (name "unconnected-(H5-GPIO81-Pad148)") (class "Default")
      (node (ref "H5") (pin "148") (pinfunction "GPIO81_148") (pintype "passive+no_connect"))
    )
    (net (code "130") (name "unconnected-(H5-GPIO82-Pad149)") (class "Default")
      (node (ref "H5") (pin "149") (pinfunction "GPIO82_149") (pintype "passive+no_connect"))
    )
    (net (code "131") (name "unconnected-(H5-GPIO83-Pad150)") (class "Default")
      (node (ref "H5") (pin "150") (pinfunction "GPIO83_150") (pintype "passive+no_connect"))
    )
    (net (code "132") (name "unconnected-(H5-GPIO84-Pad151)") (class "Default")
      (node (ref "H5") (pin "151") (pinfunction "GPIO84_151") (pintype "passive+no_connect"))
    )
    (net (code "133") (name "unconnected-(H5-GPIO85-Pad152)") (class "Default")
      (node (ref "H5") (pin "152") (pinfunction "GPIO85_152") (pintype "passive+no_connect"))
    )
    (net (code "134") (name "unconnected-(H5-GPIO86-Pad153)") (class "Default")
      (node (ref "H5") (pin "153") (pinfunction "GPIO86_153") (pintype "passive+no_connect"))
    )
    (net (code "135") (name "unconnected-(H5-GPIO87-Pad154)") (class "Default")
      (node (ref "H5") (pin "154") (pinfunction "GPIO87_154") (pintype "passive+no_connect"))
    )
    (net (code "136") (name "unconnected-(H5-GPIO89-Pad156)") (class "Default")
      (node (ref "H5") (pin "156") (pinfunction "GPIO89_156") (pintype "passive+no_connect"))
    )
    (net (code "137") (name "unconnected-(H5-GPIO90-Pad159)") (class "Default")
      (node (ref "H5") (pin "159") (pinfunction "GPIO90_159") (pintype "passive+no_connect"))
    )
    (net (code "138") (name "unconnected-(H5-GPIO91-Pad160)") (class "Default")
      (node (ref "H5") (pin "160") (pinfunction "GPIO91_160") (pintype "passive+no_connect"))
    )
    (net (code "139") (name "unconnected-(H5-GPIO92-Pad161)") (class "Default")
      (node (ref "H5") (pin "161") (pinfunction "GPIO92_161") (pintype "passive+no_connect"))
    )
    (net (code "140") (name "unconnected-(H5-GPIO93-Pad162)") (class "Default")
      (node (ref "H5") (pin "162") (pinfunction "GPIO93_162") (pintype "passive+no_connect"))
    )
    (net (code "141") (name "unconnected-(H5-GPIO94-Pad163)") (class "Default")
      (node (ref "H5") (pin "163") (pinfunction "GPIO94_163") (pintype "passive+no_connect"))
    )
    (net (code "142") (name "unconnected-(H5-GPIO120-Pad165)") (class "Default")
      (node (ref "H5") (pin "165") (pinfunction "GPIO120_165") (pintype "passive+no_connect"))
    )
    (net (code "143") (name "unconnected-(H5-GPIO121-Pad166)") (class "Default")
      (node (ref "H5") (pin "166") (pinfunction "GPIO121_166") (pintype "passive+no_connect"))
    )
    (net (code "144") (name "unconnected-(H5-GPIO133-Pad164)") (class "Default")
      (node (ref "H5") (pin "164") (pinfunction "GPIO133_164") (pintype "passive+no_connect"))
    )
    (net (code "145") (name "unconnected-(H5-GPIO161-Pad167)") (class "Default")
      (node (ref "H5") (pin "167") (pinfunction "GPIO161_167") (pintype "passive+no_connect"))
    )
    (net (code "146") (name "unconnected-(H5-GPIO162-Pad168)") (class "Default")
      (node (ref "H5") (pin "168") (pinfunction "GPIO162_168") (pintype "passive+no_connect"))
    )
    (net (code "147") (name "unconnected-(H5-GPIO163-Pad169)") (class "Default")
      (node (ref "H5") (pin "169") (pinfunction "GPIO163_169") (pintype "passive+no_connect"))
    )
    (net (code "148") (name "unconnected-(H5-GPIO164-Pad170)") (class "Default")
      (node (ref "H5") (pin "170") (pinfunction "GPIO164_170") (pintype "passive+no_connect"))
    )
    (net (code "149") (name "unconnected-(H5-NC-Pad13)") (class "Default")
      (node (ref "H5") (pin "13") (pinfunction "NC_13") (pintype "passive+no_connect"))
    )
    (net (code "150") (name "unconnected-(H5-NC-Pad16)") (class "Default")
      (node (ref "H5") (pin "16") (pinfunction "NC_16") (pintype "passive+no_connect"))
    )
    (net (code "151") (name "unconnected-(H5-NC-Pad29)") (class "Default")
      (node (ref "H5") (pin "29") (pinfunction "NC_29") (pintype "passive+no_connect"))
    )
    (net (code "152") (name "unconnected-(H5-NC-Pad32)") (class "Default")
      (node (ref "H5") (pin "32") (pinfunction "NC_32") (pintype "passive+no_connect"))
    )
    (net (code "153") (name "unconnected-(H5-NC-Pad41)") (class "Default")
      (node (ref "H5") (pin "41") (pinfunction "NC_41") (pintype "passive+no_connect"))
    )
    (net (code "154") (name "unconnected-(H5-NC-Pad43)") (class "Default")
      (node (ref "H5") (pin "43") (pinfunction "NC_43") (pintype "passive+no_connect"))
    )
    (net (code "155") (name "unconnected-(H5-NC-Pad44)") (class "Default")
      (node (ref "H5") (pin "44") (pinfunction "NC_44") (pintype "passive+no_connect"))
    )
    (net (code "156") (name "unconnected-(H5-NC-Pad66)") (class "Default")
      (node (ref "H5") (pin "66") (pinfunction "NC_66") (pintype "passive+no_connect"))
    )
    (net (code "157") (name "unconnected-(H5-NC-Pad136)") (class "Default")
      (node (ref "H5") (pin "136") (pinfunction "NC_136") (pintype "passive+no_connect"))
    )
    (net (code "158") (name "unconnected-(H5-NC-Pad178)") (class "Default")
      (node (ref "H5") (pin "178") (pinfunction "NC_178") (pintype "passive+no_connect"))
    )
    (net (code "159") (name "unconnected-(H5-QEP1-I-Pad74)") (class "Default")
      (node (ref "H5") (pin "74") (pinfunction "QEP1-I_74") (pintype "passive+no_connect"))
    )
    (net (code "160") (name "unconnected-(H5-RSV-Pad113)") (class "Default")
      (node (ref "H5") (pin "113") (pinfunction "RSV_113") (pintype "passive+no_connect"))
    )
    (net (code "161") (name "unconnected-(H5-RSV-Pad114)") (class "Default")
      (node (ref "H5") (pin "114") (pinfunction "RSV_114") (pintype "passive+no_connect"))
    )
    (net (code "162") (name "unconnected-(H5-RSV-Pad115)") (class "Default")
      (node (ref "H5") (pin "115") (pinfunction "RSV_115") (pintype "passive+no_connect"))
    )
    (net (code "163") (name "unconnected-(H5-RSV-Pad116)") (class "Default")
      (node (ref "H5") (pin "116") (pinfunction "RSV_116") (pintype "passive+no_connect"))
    )
    (net (code "164") (name "unconnected-(H5-RSV-Pad117)") (class "Default")
      (node (ref "H5") (pin "117") (pinfunction "RSV_117") (pintype "passive+no_connect"))
    )
    (net (code "165") (name "unconnected-(H5-RSV-Pad118)") (class "Default")
      (node (ref "H5") (pin "118") (pinfunction "RSV_118") (pintype "passive+no_connect"))
    )
    (net (code "166") (name "unconnected-(H5-RSV-Pad119)") (class "Default")
      (node (ref "H5") (pin "119") (pinfunction "RSV_119") (pintype "passive+no_connect"))
    )
    (net (code "167") (name "unconnected-(H5-RSV-Pad171)") (class "Default")
      (node (ref "H5") (pin "171") (pinfunction "RSV_171") (pintype "passive+no_connect"))
    )
    (net (code "168") (name "unconnected-(H5-RSV-Pad172)") (class "Default")
      (node (ref "H5") (pin "172") (pinfunction "RSV_172") (pintype "passive+no_connect"))
    )
    (net (code "169") (name "unconnected-(H5-RSV-Pad173)") (class "Default")
      (node (ref "H5") (pin "173") (pinfunction "RSV_173") (pintype "passive+no_connect"))
    )
    (net (code "170") (name "unconnected-(H5-RSV-Pad174)") (class "Default")
      (node (ref "H5") (pin "174") (pinfunction "RSV_174") (pintype "passive+no_connect"))
    )
    (net (code "171") (name "unconnected-(H5-RSV-Pad175)") (class "Default")
      (node (ref "H5") (pin "175") (pinfunction "RSV_175") (pintype "passive+no_connect"))
    )
    (net (code "172") (name "unconnected-(H5-RSV-Pad176)") (class "Default")
      (node (ref "H5") (pin "176") (pinfunction "RSV_176") (pintype "passive+no_connect"))
    )
    (net (code "173") (name "unconnected-(H5-RSV-Pad177)") (class "Default")
      (node (ref "H5") (pin "177") (pinfunction "RSV_177") (pintype "passive+no_connect"))
    )
    (net (code "174") (name "unconnected-(H5-SCIRXA-Pad76)") (class "Default")
      (node (ref "H5") (pin "76") (pinfunction "SCIRXA_76") (pintype "passive+no_connect"))
    )
    (net (code "175") (name "unconnected-(H5-SCITXA-Pad78)") (class "Default")
      (node (ref "H5") (pin "78") (pinfunction "SCITXA_78") (pintype "passive+no_connect"))
    )
    (net (code "176") (name "unconnected-(H5-TCK-Pad5)") (class "Default")
      (node (ref "H5") (pin "5") (pinfunction "TCK_5") (pintype "passive+no_connect"))
    )
    (net (code "177") (name "unconnected-(H5-TDI-Pad8)") (class "Default")
      (node (ref "H5") (pin "8") (pinfunction "TDI_8") (pintype "passive+no_connect"))
    )
    (net (code "178") (name "unconnected-(H5-TDO-Pad6)") (class "Default")
      (node (ref "H5") (pin "6") (pinfunction "TDO_6") (pintype "passive+no_connect"))
    )
    (net (code "179") (name "unconnected-(H5-TMS-Pad3)") (class "Default")
      (node (ref "H5") (pin "3") (pinfunction "TMS_3") (pintype "passive+no_connect"))
    )
    (net (code "180") (name "unconnected-(H5-TRS~{T}-Pad4)") (class "Default")
      (node (ref "H5") (pin "4") (pinfunction "TRS~{T}_4") (pintype "passive+no_connect"))
    )
    (net (code "181") (name "unconnected-(H5-VREF-HI-Pad45)") (class "Default")
      (node (ref "H5") (pin "45") (pinfunction "VREF-HI_45") (pintype "passive+no_connect"))
    )
    (net (code "182") (name "unconnected-(H5-XR~{S}-Pad120)") (class "Default")
      (node (ref "H5") (pin "120") (pinfunction "XR~{S}_120") (pintype "passive+no_connect"))
    )
    (net (code "183") (name "unconnected-(U9B-COM-Pad9)") (class "Default")
      (node (ref "U9") (pin "9") (pinfunction "COM_9") (pintype "power_in+no_connect"))
    )
  )
)
